# sensor_board_v10.net
KiCad netlist of a schematic drawn in EAGLE
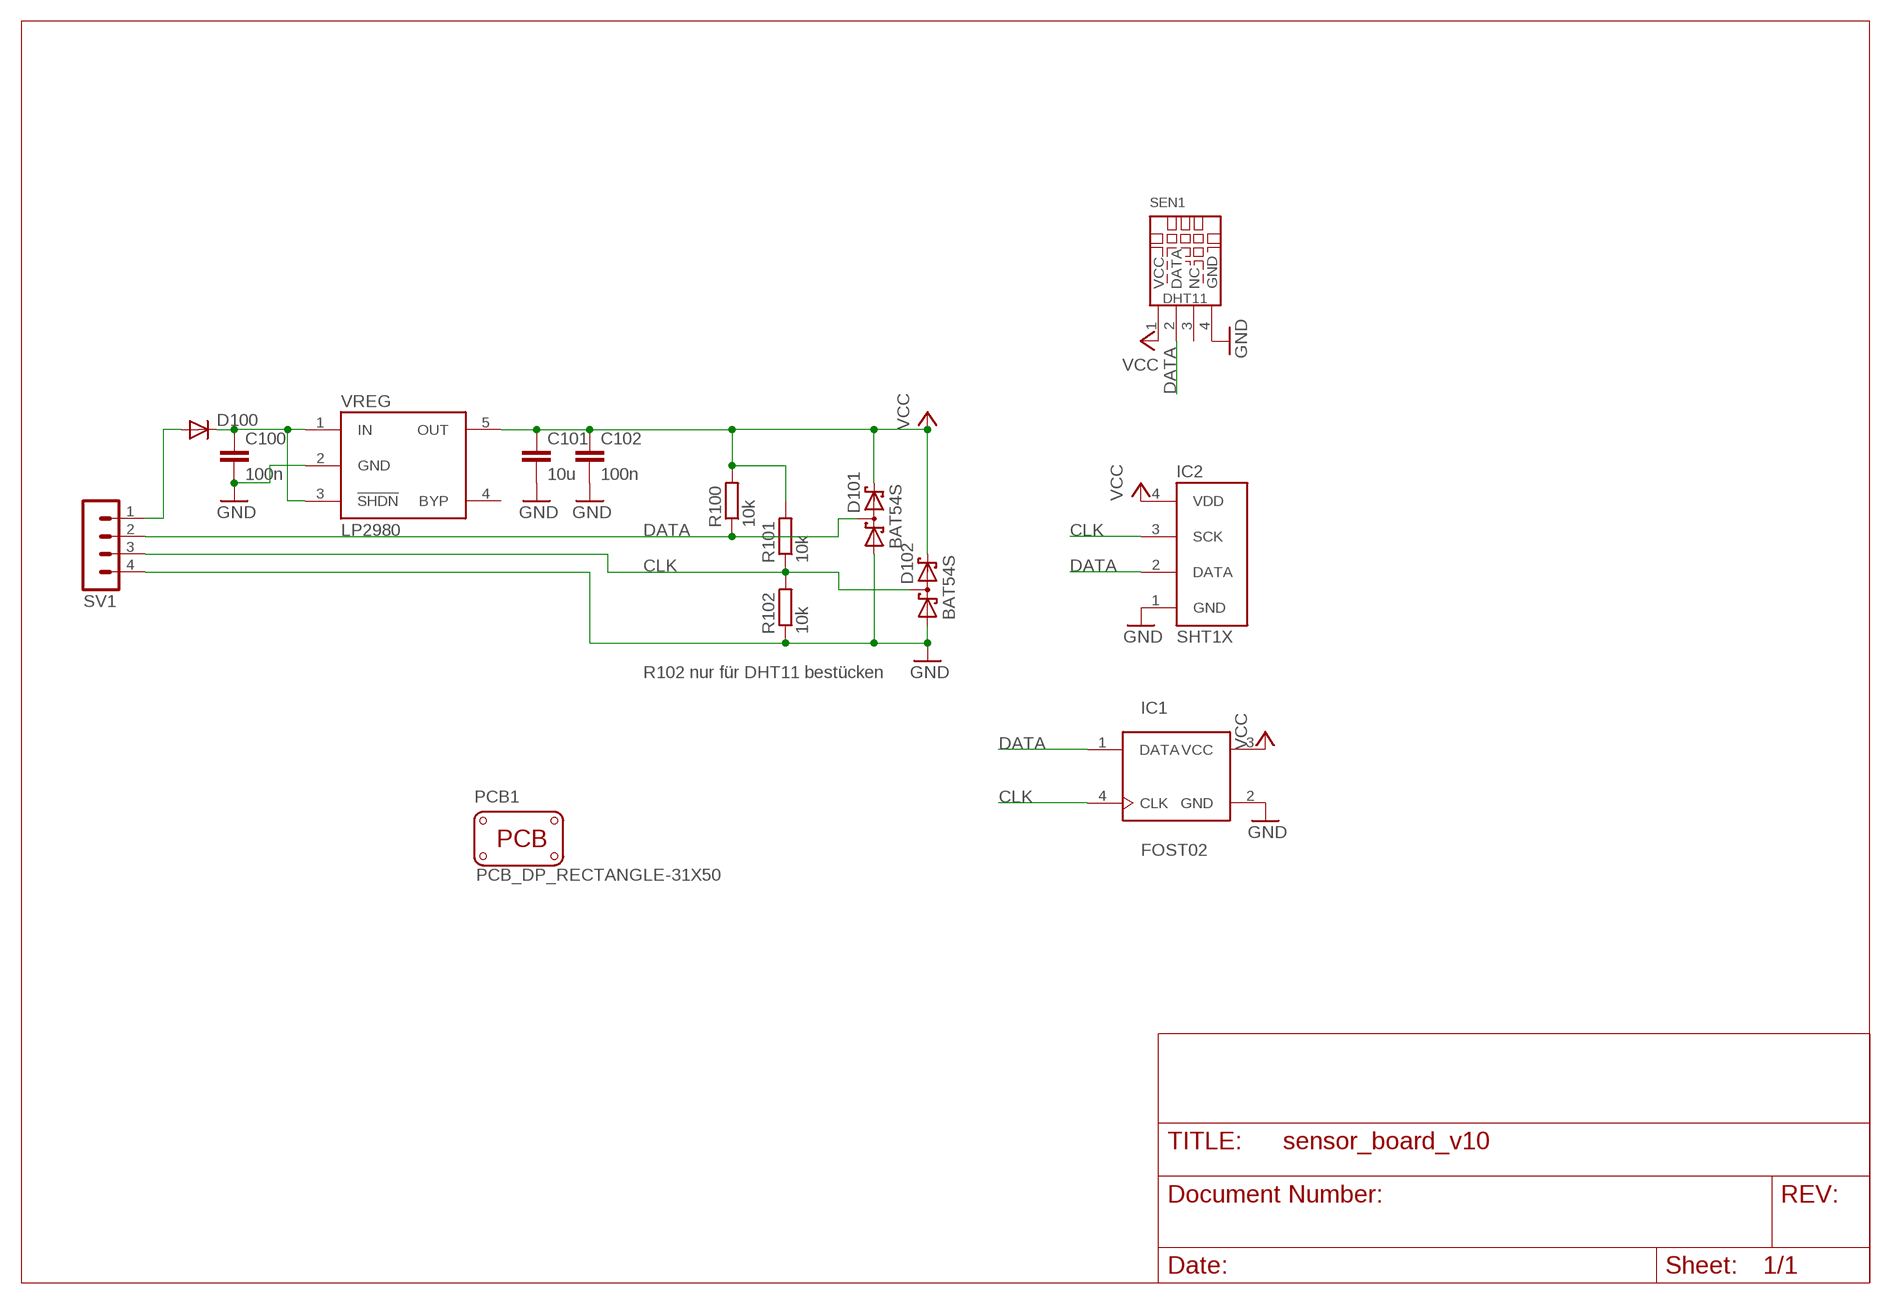
[diagram p0: schematic, sheet 1]

(export (version "E")
  (design (tool "Eeschema 10.0.6"))
  (components
    (comp (ref "C100")
      (value "100n")
      (footprint "eagle-import:C0805")
      (libsource (lib "eagle-import") (part "C-EUC0805"))
    )
    (comp (ref "C101")
      (value "10u")
      (footprint "eagle-import:C0805")
      (libsource (lib "eagle-import") (part "C-EUC0805"))
    )
    (comp (ref "C102")
      (value "100n")
      (footprint "eagle-import:C0805")
      (libsource (lib "eagle-import") (part "C-EUC0805"))
    )
    (comp (ref "D100")
      (value "DIODE-SOD123")
      (footprint "eagle-import:SOD123")
      (libsource (lib "eagle-import") (part "DIODE-SOD123"))
    )
    (comp (ref "D101")
      (value "BAT54S")
      (footprint "eagle-import:SOT23")
      (libsource (lib "eagle-import") (part "BAT54S"))
    )
    (comp (ref "D102")
      (value "BAT54S")
      (footprint "eagle-import:SOT23")
      (libsource (lib "eagle-import") (part "BAT54S"))
    )
    (comp (ref "IC1")
      (value "FOST02")
      (footprint "eagle-import:FOST02")
      (libsource (lib "eagle-import") (part "FOST02"))
    )
    (comp (ref "IC2")
      (value "SHT1X")
      (footprint "eagle-import:SHT1X")
      (libsource (lib "eagle-import") (part "SHT1X"))
    )
    (comp (ref "PCB1")
      (value "PCB_DP_RECTANGLE-31X50")
      (footprint "eagle-import:DP5031_V1")
      (libsource (lib "eagle-import") (part "PCB_DP_RECTANGLE-31X50"))
    )
    (comp (ref "R100")
      (value "10k")
      (footprint "eagle-import:R0805")
      (libsource (lib "eagle-import") (part "R-EU_R0805"))
    )
    (comp (ref "R101")
      (value "10k")
      (footprint "eagle-import:R0805")
      (libsource (lib "eagle-import") (part "R-EU_R0805"))
    )
    (comp (ref "R102")
      (value "10k")
      (footprint "eagle-import:R0805")
      (libsource (lib "eagle-import") (part "R-EU_R0805"))
    )
    (comp (ref "SEN1")
      (value "DHT11")
      (footprint "eagle-import:DHT11")
      (libsource (lib "eagle-import") (part "DHT11"))
    )
    (comp (ref "SV1")
      (value "MA04-1")
      (footprint "eagle-import:MA04-1")
      (libsource (lib "eagle-import") (part "MA04-1"))
    )
    (comp (ref "VREG")
      (value "LP2980")
      (footprint "eagle-import:SOT-23-5")
      (libsource (lib "eagle-import") (part "TC1185-SOT-23-5"))
    )
  )
  (nets
    (net (code "1") (name "/CLK") (class "Default")
      (node (ref "D102") (pin "3") (pinfunction "C1A2_3") (pintype "passive"))
      (node (ref "IC1") (pin "4") (pinfunction "CLK_4") (pintype "input"))
      (node (ref "IC2") (pin "3") (pinfunction "SCK_3") (pintype "input"))
      (node (ref "R101") (pin "1") (pinfunction "1_1") (pintype "passive"))
      (node (ref "R102") (pin "2") (pinfunction "2_2") (pintype "passive"))
      (node (ref "SV1") (pin "3") (pinfunction "3_3") (pintype "passive"))
    )
    (net (code "2") (name "/DATA") (class "Default")
      (node (ref "D101") (pin "3") (pinfunction "C1A2_3") (pintype "passive"))
      (node (ref "IC1") (pin "1") (pinfunction "DATA_1") (pintype "bidirectional"))
      (node (ref "IC2") (pin "2") (pinfunction "DATA_2") (pintype "open_collector"))
      (node (ref "R100") (pin "1") (pinfunction "1_1") (pintype "passive"))
      (node (ref "SEN1") (pin "2") (pinfunction "DATA_2") (pintype "bidirectional"))
      (node (ref "SV1") (pin "2") (pinfunction "2_2") (pintype "passive"))
    )
    (net (code "3") (name "GND") (class "Default")
      (node (ref "C100") (pin "2") (pinfunction "2_2") (pintype "passive"))
      (node (ref "C101") (pin "2") (pinfunction "2_2") (pintype "passive"))
      (node (ref "C102") (pin "2") (pinfunction "2_2") (pintype "passive"))
      (node (ref "D101") (pin "1") (pinfunction "A1_1") (pintype "passive"))
      (node (ref "D102") (pin "1") (pinfunction "A1_1") (pintype "passive"))
      (node (ref "IC1") (pin "2") (pinfunction "GND_2") (pintype "power_in"))
      (node (ref "IC2") (pin "1") (pinfunction "GND_1") (pintype "power_in"))
      (node (ref "R102") (pin "1") (pinfunction "1_1") (pintype "passive"))
      (node (ref "SEN1") (pin "4") (pinfunction "GND_4") (pintype "power_in"))
      (node (ref "SV1") (pin "4") (pinfunction "4_4") (pintype "passive"))
      (node (ref "VREG") (pin "2") (pinfunction "GND_2") (pintype "power_in"))
    )
    (net (code "4") (name "Net-(D100-PadA)") (class "Default")
      (node (ref "D100") (pin "A") (pinfunction "A_A") (pintype "passive"))
      (node (ref "SV1") (pin "1") (pinfunction "1_1") (pintype "passive"))
    )
    (net (code "5") (name "Net-(VREG-IN)") (class "Default")
      (node (ref "C100") (pin "1") (pinfunction "1_1") (pintype "passive"))
      (node (ref "D100") (pin "C") (pinfunction "C_C") (pintype "passive"))
      (node (ref "VREG") (pin "1") (pinfunction "IN_1") (pintype "power_in"))
      (node (ref "VREG") (pin "3") (pinfunction "~{SHDN}_3") (pintype "bidirectional"))
    )
    (net (code "6") (name "VCC") (class "Default")
      (node (ref "C101") (pin "1") (pinfunction "1_1") (pintype "passive"))
      (node (ref "C102") (pin "1") (pinfunction "1_1") (pintype "passive"))
      (node (ref "D101") (pin "2") (pinfunction "C2_2") (pintype "passive"))
      (node (ref "D102") (pin "2") (pinfunction "C2_2") (pintype "passive"))
      (node (ref "IC1") (pin "3") (pinfunction "VCC_3") (pintype "power_in"))
      (node (ref "IC2") (pin "4") (pinfunction "VDD_4") (pintype "power_in"))
      (node (ref "R100") (pin "2") (pinfunction "2_2") (pintype "passive"))
      (node (ref "R101") (pin "2") (pinfunction "2_2") (pintype "passive"))
      (node (ref "SEN1") (pin "1") (pinfunction "VCC_1") (pintype "power_in"))
      (node (ref "VREG") (pin "5") (pinfunction "OUT_5") (pintype "power_in"))
    )
    (net (code "7") (name "unconnected-(SEN1-NC-Pad3)") (class "Default")
      (node (ref "SEN1") (pin "3") (pinfunction "NC_3") (pintype "no_connect"))
    )
    (net (code "8") (name "unconnected-(VREG-BYP-Pad4)") (class "Default")
      (node (ref "VREG") (pin "4") (pinfunction "BYP_4") (pintype "bidirectional"))
    )
  )
)
